# USB_SWITCH_A.net
KiCad netlist of a schematic drawn in Altium Designer
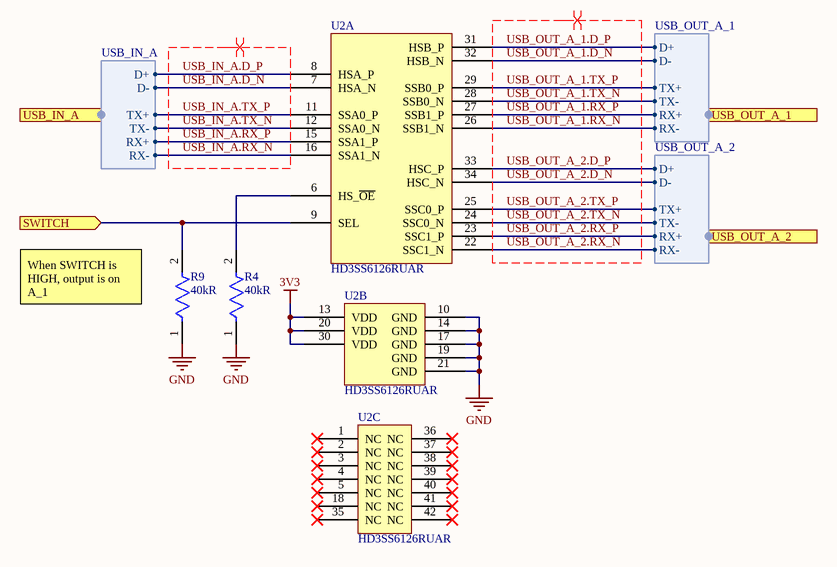
[diagram p0: USB_SWITCH_A.SchDoc]

(export (version "E")
  (design (tool "Eeschema 10.0.6"))
  (components
    (comp (ref "R4")
      (value "CRCW080540K0FKEA")
      (footprint "FP-CRCW0805-e3-MFG")
      (description "RES Thick Film, 40kΩ, 1%, 0.125W, 100ppm/°C, 0805")
      (fields (field (name "TOLERANCE") "1%") (field (name "RESISTANCE") "40kR"))
      (libsource (lib "Altium Content Vault") (part "1029c3af85768c4190bb7ad29bc67b5"))
    )
    (comp (ref "R9")
      (value "CRCW080540K0FKEA")
      (footprint "FP-CRCW0805-e3-MFG")
      (description "RES Thick Film, 40kΩ, 1%, 0.125W, 100ppm/°C, 0805")
      (fields (field (name "TOLERANCE") "1%") (field (name "RESISTANCE") "40kR"))
      (libsource (lib "Altium Content Vault") (part "1029c3af85768c4190bb7ad29bc67b5"))
    )
    (comp (ref "U2")
      (value "HD3SS6126RUAR")
      (footprint "QFN50P900X350X80-43N")
      (description "High Speed Differential Switch 2: 1/1: 2 MUX/DEMUX USB 2.0/USB 3.0 3.3V T/R 42-Pin WQFN EP")
      (libsource (lib "KVM Symbols") (part "HD3SS6126RUAR"))
    )
  )
  (nets
    (net (code "4") (name "/SWITCH") (class "Default")
      (node (ref "R9") (pin "2") (pinfunction "2_2") (pintype "passive"))
      (node (ref "U2") (pin "9") (pinfunction "SEL_9") (pintype "passive"))
    )
    (net (code "5") (name "/USB_IN_A.D_N") (class "Default")
      (node (ref "U2") (pin "7") (pinfunction "HSA_N_7") (pintype "passive"))
    )
    (net (code "6") (name "/USB_IN_A.D_P") (class "Default")
      (node (ref "U2") (pin "8") (pinfunction "HSA_P_8") (pintype "passive"))
    )
    (net (code "7") (name "/USB_IN_A.RX_N") (class "Default")
      (node (ref "U2") (pin "16") (pinfunction "SSA1_N_16") (pintype "passive"))
    )
    (net (code "8") (name "/USB_IN_A.RX_P") (class "Default")
      (node (ref "U2") (pin "15") (pinfunction "SSA1_P_15") (pintype "passive"))
    )
    (net (code "9") (name "/USB_IN_A.TX_N") (class "Default")
      (node (ref "U2") (pin "12") (pinfunction "SSA0_N_12") (pintype "passive"))
    )
    (net (code "10") (name "/USB_IN_A.TX_P") (class "Default")
      (node (ref "U2") (pin "11") (pinfunction "SSA0_P_11") (pintype "passive"))
    )
    (net (code "11") (name "/USB_OUT_A_1.D_N") (class "Default")
      (node (ref "U2") (pin "32") (pinfunction "HSB_N_32") (pintype "passive"))
    )
    (net (code "12") (name "/USB_OUT_A_1.D_P") (class "Default")
      (node (ref "U2") (pin "31") (pinfunction "HSB_P_31") (pintype "passive"))
    )
    (net (code "13") (name "/USB_OUT_A_1.RX_N") (class "Default")
      (node (ref "U2") (pin "26") (pinfunction "SSB1_N_26") (pintype "passive"))
    )
    (net (code "14") (name "/USB_OUT_A_1.RX_P") (class "Default")
      (node (ref "U2") (pin "27") (pinfunction "SSB1_P_27") (pintype "passive"))
    )
    (net (code "15") (name "/USB_OUT_A_1.TX_N") (class "Default")
      (node (ref "U2") (pin "28") (pinfunction "SSB0_N_28") (pintype "passive"))
    )
    (net (code "16") (name "/USB_OUT_A_1.TX_P") (class "Default")
      (node (ref "U2") (pin "29") (pinfunction "SSB0_P_29") (pintype "passive"))
    )
    (net (code "17") (name "/USB_OUT_A_2.D_N") (class "Default")
      (node (ref "U2") (pin "34") (pinfunction "HSC_N_34") (pintype "passive"))
    )
    (net (code "18") (name "/USB_OUT_A_2.D_P") (class "Default")
      (node (ref "U2") (pin "33") (pinfunction "HSC_P_33") (pintype "passive"))
    )
    (net (code "19") (name "/USB_OUT_A_2.RX_N") (class "Default")
      (node (ref "U2") (pin "22") (pinfunction "SSC1_N_22") (pintype "passive"))
    )
    (net (code "20") (name "/USB_OUT_A_2.RX_P") (class "Default")
      (node (ref "U2") (pin "23") (pinfunction "SSC1_P_23") (pintype "passive"))
    )
    (net (code "21") (name "/USB_OUT_A_2.TX_N") (class "Default")
      (node (ref "U2") (pin "24") (pinfunction "SSC0_N_24") (pintype "passive"))
    )
    (net (code "22") (name "/USB_OUT_A_2.TX_P") (class "Default")
      (node (ref "U2") (pin "25") (pinfunction "SSC0_P_25") (pintype "passive"))
    )
    (net (code "26") (name "3V3") (class "Default")
      (node (ref "U2") (pin "13") (pinfunction "VDD_13") (pintype "passive"))
      (node (ref "U2") (pin "20") (pinfunction "VDD_20") (pintype "passive"))
      (node (ref "U2") (pin "30") (pinfunction "VDD_30") (pintype "passive"))
    )
    (net (code "27") (name "GND") (class "Default")
      (node (ref "R4") (pin "1") (pinfunction "1_1") (pintype "passive"))
      (node (ref "R9") (pin "1") (pinfunction "1_1") (pintype "passive"))
      (node (ref "U2") (pin "10") (pinfunction "GND_10") (pintype "passive"))
      (node (ref "U2") (pin "14") (pinfunction "GND_14") (pintype "passive"))
      (node (ref "U2") (pin "17") (pinfunction "GND_17") (pintype "passive"))
      (node (ref "U2") (pin "19") (pinfunction "GND_19") (pintype "passive"))
      (node (ref "U2") (pin "21") (pinfunction "GND_21") (pintype "passive"))
    )
    (net (code "28") (name "Net-(U2A-HS_~{OE})") (class "Default")
      (node (ref "R4") (pin "2") (pinfunction "2_2") (pintype "passive"))
      (node (ref "U2") (pin "6") (pinfunction "HS_~{OE}_6") (pintype "passive"))
    )
    (net (code "29") (name "unconnected-(U2C-NC-Pad1)") (class "Default")
      (node (ref "U2") (pin "1") (pinfunction "NC_1") (pintype "passive+no_connect"))
    )
    (net (code "30") (name "unconnected-(U2C-NC-Pad2)") (class "Default")
      (node (ref "U2") (pin "2") (pinfunction "NC_2") (pintype "passive+no_connect"))
    )
    (net (code "31") (name "unconnected-(U2C-NC-Pad3)") (class "Default")
      (node (ref "U2") (pin "3") (pinfunction "NC_3") (pintype "passive+no_connect"))
    )
    (net (code "32") (name "unconnected-(U2C-NC-Pad4)") (class "Default")
      (node (ref "U2") (pin "4") (pinfunction "NC_4") (pintype "passive+no_connect"))
    )
    (net (code "33") (name "unconnected-(U2C-NC-Pad5)") (class "Default")
      (node (ref "U2") (pin "5") (pinfunction "NC_5") (pintype "passive+no_connect"))
    )
    (net (code "34") (name "unconnected-(U2C-NC-Pad18)") (class "Default")
      (node (ref "U2") (pin "18") (pinfunction "NC_18") (pintype "passive+no_connect"))
    )
    (net (code "35") (name "unconnected-(U2C-NC-Pad35)") (class "Default")
      (node (ref "U2") (pin "35") (pinfunction "NC_35") (pintype "passive+no_connect"))
    )
    (net (code "36") (name "unconnected-(U2C-NC-Pad36)") (class "Default")
      (node (ref "U2") (pin "36") (pinfunction "NC_36") (pintype "passive+no_connect"))
    )
    (net (code "37") (name "unconnected-(U2C-NC-Pad37)") (class "Default")
      (node (ref "U2") (pin "37") (pinfunction "NC_37") (pintype "passive+no_connect"))
    )
    (net (code "38") (name "unconnected-(U2C-NC-Pad38)") (class "Default")
      (node (ref "U2") (pin "38") (pinfunction "NC_38") (pintype "passive+no_connect"))
    )
    (net (code "39") (name "unconnected-(U2C-NC-Pad39)") (class "Default")
      (node (ref "U2") (pin "39") (pinfunction "NC_39") (pintype "passive+no_connect"))
    )
    (net (code "40") (name "unconnected-(U2C-NC-Pad40)") (class "Default")
      (node (ref "U2") (pin "40") (pinfunction "NC_40") (pintype "passive+no_connect"))
    )
    (net (code "41") (name "unconnected-(U2C-NC-Pad41)") (class "Default")
      (node (ref "U2") (pin "41") (pinfunction "NC_41") (pintype "passive+no_connect"))
    )
    (net (code "42") (name "unconnected-(U2C-NC-Pad42)") (class "Default")
      (node (ref "U2") (pin "42") (pinfunction "NC_42") (pintype "passive+no_connect"))
    )
  )
)
